# Pulsox.net
KiCad netlist of a schematic drawn in EAGLE
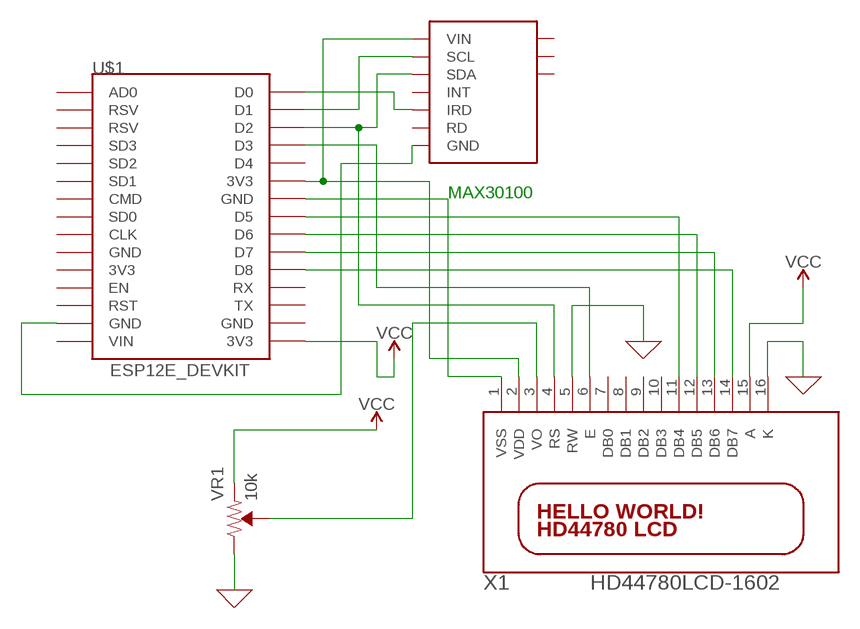
[diagram p0: schematic, sheet 1]

(export (version "E")
  (design (tool "Eeschema 10.0.6"))
  (components
    (comp (ref "MAX30100")
      (value "MAX30100")
      (footprint "eagle-import:MAX30100")
      (libsource (lib "eagle-import") (part "MAX30100"))
    )
    (comp (ref "U$1")
      (value "ESP12E_DEVKIT")
      (footprint "eagle-import:ESP12E_DEVKIT")
      (libsource (lib "eagle-import") (part "ESP12E_DEVKIT"))
    )
    (comp (ref "VR1")
      (value "10k")
      (footprint "eagle-import:TRIMPOT-PTH-3386U")
      (libsource (lib "eagle-import") (part "TRIMPOT-PTH-10MM-KNOB-1/2W-10%"))
    )
    (comp (ref "X1")
      (value "HD44780LCD-1602")
      (footprint "eagle-import:LCD1602")
      (libsource (lib "eagle-import") (part "HD44780LCD-1602"))
    )
  )
  (nets
    (net (code "1") (name "GND") (class "Default")
      (node (ref "VR1") (pin "3") (pinfunction "CW_3") (pintype "passive"))
      (node (ref "X1") (pin "16") (pinfunction "K_16") (pintype "input"))
      (node (ref "X1") (pin "5") (pinfunction "RW_5") (pintype "input"))
    )
    (net (code "2") (name "Net-(MAX30100-GND)") (class "Default")
      (node (ref "MAX30100") (pin "9") (pinfunction "GND_9") (pintype "bidirectional"))
      (node (ref "U$1") (pin "GND@1") (pinfunction "GND_GND@1") (pintype "bidirectional"))
    )
    (net (code "3") (name "Net-(MAX30100-IRD)") (class "Default")
      (node (ref "MAX30100") (pin "6") (pinfunction "IRD_6") (pintype "bidirectional"))
      (node (ref "U$1") (pin "D0") (pinfunction "D0_D0") (pintype "bidirectional"))
    )
    (net (code "4") (name "Net-(MAX30100-SCL)") (class "Default")
      (node (ref "MAX30100") (pin "3") (pinfunction "SCL_3") (pintype "bidirectional"))
      (node (ref "U$1") (pin "D1") (pinfunction "D1_D1") (pintype "bidirectional"))
    )
    (net (code "5") (name "Net-(MAX30100-SDA)") (class "Default")
      (node (ref "MAX30100") (pin "4") (pinfunction "SDA_4") (pintype "bidirectional"))
      (node (ref "U$1") (pin "D2") (pinfunction "D2_D2") (pintype "bidirectional"))
      (node (ref "X1") (pin "4") (pinfunction "RS_4") (pintype "input"))
    )
    (net (code "6") (name "Net-(MAX30100-VIN)") (class "Default")
      (node (ref "MAX30100") (pin "2") (pinfunction "VIN_2") (pintype "bidirectional"))
      (node (ref "U$1") (pin "3V3@1") (pinfunction "3V3_3V3@1") (pintype "bidirectional"))
      (node (ref "X1") (pin "2") (pinfunction "VDD_2") (pintype "power_in"))
    )
    (net (code "7") (name "Net-(VR1-WIPER)") (class "Default")
      (node (ref "VR1") (pin "2") (pinfunction "WIPER_2") (pintype "passive"))
      (node (ref "X1") (pin "3") (pinfunction "VO_3") (pintype "input"))
    )
    (net (code "8") (name "Net-(X1-DB4)") (class "Default")
      (node (ref "U$1") (pin "D5") (pinfunction "D5_D5") (pintype "bidirectional"))
      (node (ref "X1") (pin "11") (pinfunction "DB4_11") (pintype "bidirectional"))
    )
    (net (code "9") (name "Net-(X1-DB5)") (class "Default")
      (node (ref "U$1") (pin "D6") (pinfunction "D6_D6") (pintype "bidirectional"))
      (node (ref "X1") (pin "12") (pinfunction "DB5_12") (pintype "bidirectional"))
    )
    (net (code "10") (name "Net-(X1-DB6)") (class "Default")
      (node (ref "U$1") (pin "D7") (pinfunction "D7_D7") (pintype "bidirectional"))
      (node (ref "X1") (pin "13") (pinfunction "DB6_13") (pintype "bidirectional"))
    )
    (net (code "11") (name "Net-(X1-DB7)") (class "Default")
      (node (ref "U$1") (pin "D8") (pinfunction "D8_D8") (pintype "bidirectional"))
      (node (ref "X1") (pin "14") (pinfunction "DB7_14") (pintype "bidirectional"))
    )
    (net (code "12") (name "Net-(X1-E)") (class "Default")
      (node (ref "U$1") (pin "D3") (pinfunction "D3_D3") (pintype "bidirectional"))
      (node (ref "X1") (pin "6") (pinfunction "E_6") (pintype "input"))
    )
    (net (code "13") (name "Net-(X1-VSS)") (class "Default")
      (node (ref "U$1") (pin "GND@2") (pinfunction "GND_GND@2") (pintype "bidirectional"))
      (node (ref "X1") (pin "1") (pinfunction "VSS_1") (pintype "power_in"))
    )
    (net (code "14") (name "VCC") (class "Default")
      (node (ref "U$1") (pin "3V3@2") (pinfunction "3V3_3V3@2") (pintype "bidirectional"))
      (node (ref "VR1") (pin "1") (pinfunction "CCW_1") (pintype "passive"))
      (node (ref "X1") (pin "15") (pinfunction "A_15") (pintype "input"))
    )
    (net (code "15") (name "unconnected-(MAX30100-1-Pad13)") (class "Default")
      (node (ref "MAX30100") (pin "13") (pinfunction "1_13") (pintype "bidirectional"))
    )
    (net (code "16") (name "unconnected-(MAX30100-2-Pad12)") (class "Default")
      (node (ref "MAX30100") (pin "12") (pinfunction "2_12") (pintype "bidirectional"))
    )
    (net (code "17") (name "unconnected-(MAX30100-3-Pad11)") (class "Default")
      (node (ref "MAX30100") (pin "11") (pinfunction "3_11") (pintype "bidirectional"))
    )
    (net (code "18") (name "unconnected-(MAX30100-INT-Pad5)") (class "Default")
      (node (ref "MAX30100") (pin "5") (pinfunction "INT_5") (pintype "bidirectional"))
    )
    (net (code "19") (name "unconnected-(MAX30100-RD-Pad10)") (class "Default")
      (node (ref "MAX30100") (pin "10") (pinfunction "RD_10") (pintype "bidirectional"))
    )
    (net (code "20") (name "unconnected-(U$1-3V3-Pad3V3@0)") (class "Default")
      (node (ref "U$1") (pin "3V3@0") (pinfunction "3V3_3V3@0") (pintype "bidirectional"))
    )
    (net (code "21") (name "unconnected-(U$1-GND-PadGND@0)") (class "Default")
      (node (ref "U$1") (pin "GND@0") (pinfunction "GND_GND@0") (pintype "bidirectional"))
    )
    (net (code "22") (name "unconnected-(U$1-GND-PadGND@3)") (class "Default")
      (node (ref "U$1") (pin "GND@3") (pinfunction "GND_GND@3") (pintype "bidirectional"))
    )
    (net (code "23") (name "unconnected-(U$1-PadAD0)") (class "Default")
      (node (ref "U$1") (pin "AD0") (pinfunction "AD0_AD0") (pintype "bidirectional"))
    )
    (net (code "24") (name "unconnected-(U$1-PadCLK)") (class "Default")
      (node (ref "U$1") (pin "CLK") (pinfunction "CLK_CLK") (pintype "bidirectional"))
    )
    (net (code "25") (name "unconnected-(U$1-PadCMD)") (class "Default")
      (node (ref "U$1") (pin "CMD") (pinfunction "CMD_CMD") (pintype "bidirectional"))
    )
    (net (code "26") (name "unconnected-(U$1-PadD4)") (class "Default")
      (node (ref "U$1") (pin "D4") (pinfunction "D4_D4") (pintype "bidirectional"))
    )
    (net (code "27") (name "unconnected-(U$1-PadEN)") (class "Default")
      (node (ref "U$1") (pin "EN") (pinfunction "EN_EN") (pintype "bidirectional"))
    )
    (net (code "28") (name "unconnected-(U$1-PadRST)") (class "Default")
      (node (ref "U$1") (pin "RST") (pinfunction "RST_RST") (pintype "bidirectional"))
    )
    (net (code "29") (name "unconnected-(U$1-PadRX)") (class "Default")
      (node (ref "U$1") (pin "RX") (pinfunction "RX_RX") (pintype "bidirectional"))
    )
    (net (code "30") (name "unconnected-(U$1-PadSD0)") (class "Default")
      (node (ref "U$1") (pin "SD0") (pinfunction "SD0_SD0") (pintype "bidirectional"))
    )
    (net (code "31") (name "unconnected-(U$1-PadSD1)") (class "Default")
      (node (ref "U$1") (pin "SD1") (pinfunction "SD1_SD1") (pintype "bidirectional"))
    )
    (net (code "32") (name "unconnected-(U$1-PadSD2)") (class "Default")
      (node (ref "U$1") (pin "SD2") (pinfunction "SD2_SD2") (pintype "bidirectional"))
    )
    (net (code "33") (name "unconnected-(U$1-PadSD3)") (class "Default")
      (node (ref "U$1") (pin "SD3") (pinfunction "SD3_SD3") (pintype "bidirectional"))
    )
    (net (code "34") (name "unconnected-(U$1-PadTX)") (class "Default")
      (node (ref "U$1") (pin "TX") (pinfunction "TX_TX") (pintype "bidirectional"))
    )
    (net (code "35") (name "unconnected-(U$1-PadVIN)") (class "Default")
      (node (ref "U$1") (pin "VIN") (pinfunction "VIN_VIN") (pintype "bidirectional"))
    )
    (net (code "36") (name "unconnected-(U$1-RSV-PadRSV@0)") (class "Default")
      (node (ref "U$1") (pin "RSV@0") (pinfunction "RSV_RSV@0") (pintype "bidirectional"))
    )
    (net (code "37") (name "unconnected-(U$1-RSV-PadRSV@1)") (class "Default")
      (node (ref "U$1") (pin "RSV@1") (pinfunction "RSV_RSV@1") (pintype "bidirectional"))
    )
    (net (code "38") (name "unconnected-(X1-DB0-Pad7)") (class "Default")
      (node (ref "X1") (pin "7") (pinfunction "DB0_7") (pintype "bidirectional"))
    )
    (net (code "39") (name "unconnected-(X1-DB1-Pad8)") (class "Default")
      (node (ref "X1") (pin "8") (pinfunction "DB1_8") (pintype "bidirectional"))
    )
    (net (code "40") (name "unconnected-(X1-DB2-Pad9)") (class "Default")
      (node (ref "X1") (pin "9") (pinfunction "DB2_9") (pintype "bidirectional"))
    )
    (net (code "41") (name "unconnected-(X1-DB3-Pad10)") (class "Default")
      (node (ref "X1") (pin "10") (pinfunction "DB3_10") (pintype "bidirectional"))
    )
  )
)
